# 2_waffling60-DB_matrix.net
KiCad netlist of a schematic drawn in Altium Designer
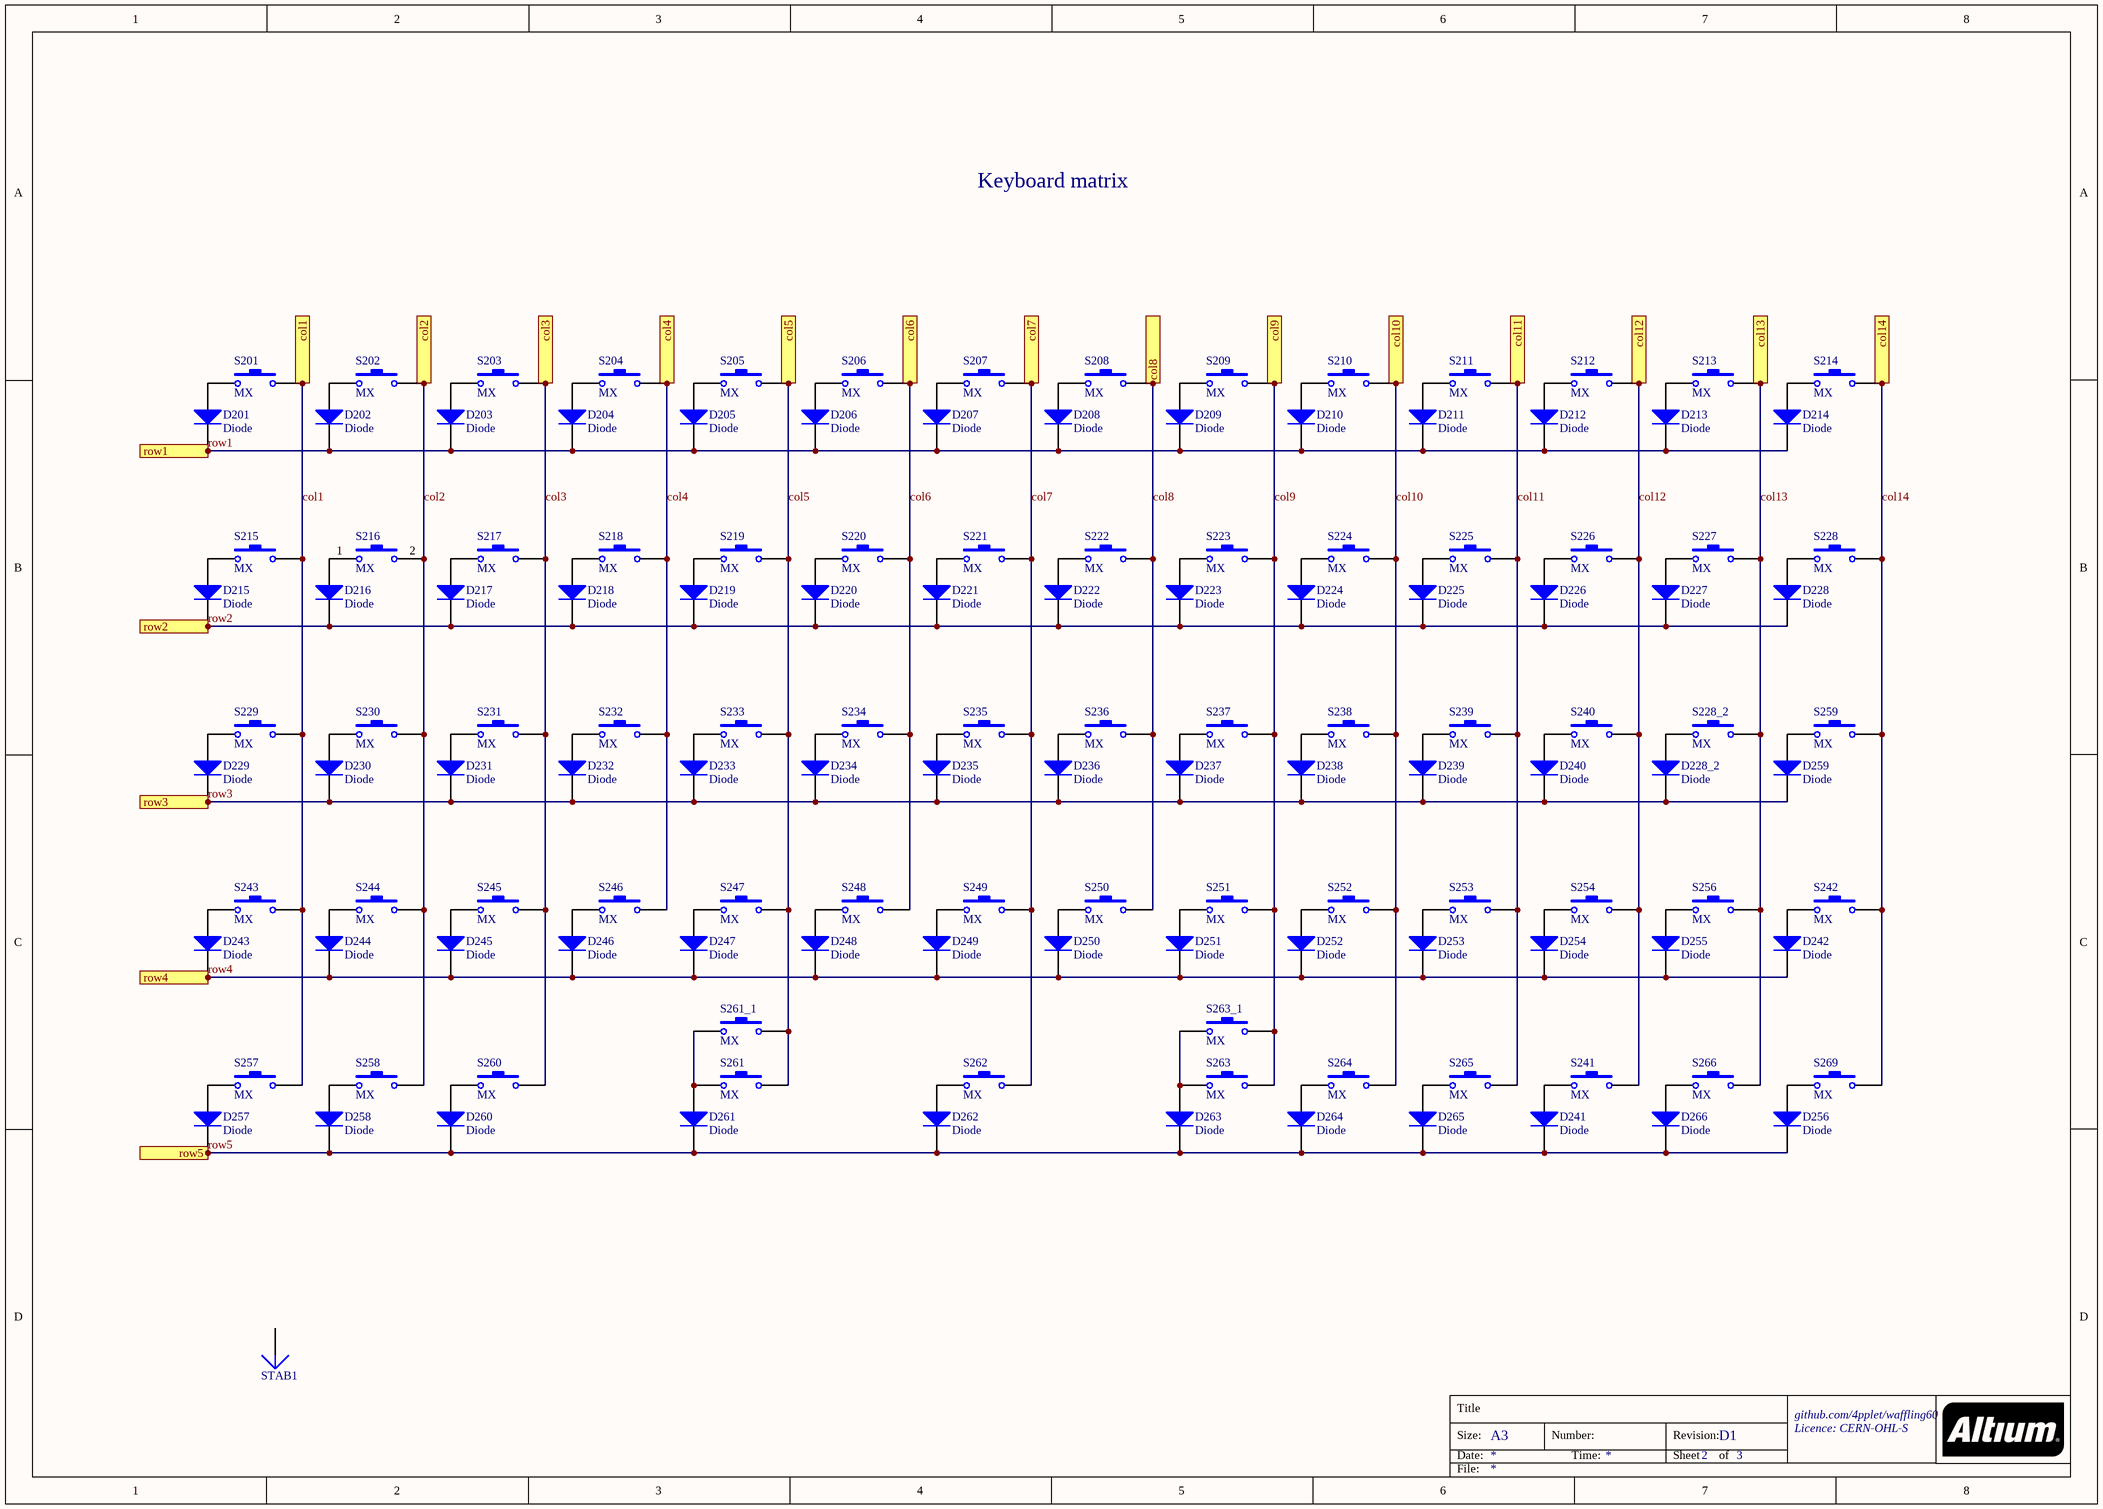
[diagram p0: 2_waffling60-DB_matrix.SchDoc]

(export (version "E")
  (design (tool "Eeschema 10.0.6"))
  (components
    (comp (ref "D201")
      (value "Diode")
      (footprint "SOD-123")
      (description "Default Diode")
      (fields (field (name "LCSC PART #") "C81598") (field (name "MRF.PART") "1N4148W"))
      (libsource (lib "Miscellaneous Devices") (part "Diode"))
    )
    (comp (ref "D202")
      (value "Diode")
      (footprint "SOD-123")
      (description "Default Diode")
      (fields (field (name "LCSC PART #") "C81598") (field (name "MRF.PART") "1N4148W"))
      (libsource (lib "Miscellaneous Devices") (part "Diode"))
    )
    (comp (ref "D203")
      (value "Diode")
      (footprint "SOD-123")
      (description "Default Diode")
      (fields (field (name "LCSC PART #") "C81598") (field (name "MRF.PART") "1N4148W"))
      (libsource (lib "Miscellaneous Devices") (part "Diode"))
    )
    (comp (ref "D204")
      (value "Diode")
      (footprint "SOD-123")
      (description "Default Diode")
      (fields (field (name "LCSC PART #") "C81598") (field (name "MRF.PART") "1N4148W"))
      (libsource (lib "Miscellaneous Devices") (part "Diode"))
    )
    (comp (ref "D205")
      (value "Diode")
      (footprint "SOD-123")
      (description "Default Diode")
      (fields (field (name "LCSC PART #") "C81598") (field (name "MRF.PART") "1N4148W"))
      (libsource (lib "Miscellaneous Devices") (part "Diode"))
    )
    (comp (ref "D206")
      (value "Diode")
      (footprint "SOD-123")
      (description "Default Diode")
      (fields (field (name "LCSC PART #") "C81598") (field (name "MRF.PART") "1N4148W"))
      (libsource (lib "Miscellaneous Devices") (part "Diode"))
    )
    (comp (ref "D207")
      (value "Diode")
      (footprint "SOD-123")
      (description "Default Diode")
      (fields (field (name "LCSC PART #") "C81598") (field (name "MRF.PART") "1N4148W"))
      (libsource (lib "Miscellaneous Devices") (part "Diode"))
    )
    (comp (ref "D208")
      (value "Diode")
      (footprint "SOD-123")
      (description "Default Diode")
      (fields (field (name "LCSC PART #") "C81598") (field (name "MRF.PART") "1N4148W"))
      (libsource (lib "Miscellaneous Devices") (part "Diode"))
    )
    (comp (ref "D209")
      (value "Diode")
      (footprint "SOD-123")
      (description "Default Diode")
      (fields (field (name "LCSC PART #") "C81598") (field (name "MRF.PART") "1N4148W"))
      (libsource (lib "Miscellaneous Devices") (part "Diode"))
    )
    (comp (ref "D210")
      (value "Diode")
      (footprint "SOD-123")
      (description "Default Diode")
      (fields (field (name "LCSC PART #") "C81598") (field (name "MRF.PART") "1N4148W"))
      (libsource (lib "Miscellaneous Devices") (part "Diode"))
    )
    (comp (ref "D211")
      (value "Diode")
      (footprint "SOD-123")
      (description "Default Diode")
      (fields (field (name "LCSC PART #") "C81598") (field (name "MRF.PART") "1N4148W"))
      (libsource (lib "Miscellaneous Devices") (part "Diode"))
    )
    (comp (ref "D212")
      (value "Diode")
      (footprint "SOD-123")
      (description "Default Diode")
      (fields (field (name "LCSC PART #") "C81598") (field (name "MRF.PART") "1N4148W"))
      (libsource (lib "Miscellaneous Devices") (part "Diode"))
    )
    (comp (ref "D213")
      (value "Diode")
      (footprint "SOD-123")
      (description "Default Diode")
      (fields (field (name "LCSC PART #") "C81598") (field (name "MRF.PART") "1N4148W"))
      (libsource (lib "Miscellaneous Devices") (part "Diode"))
    )
    (comp (ref "D214")
      (value "Diode")
      (footprint "SOD-123")
      (description "Default Diode")
      (fields (field (name "LCSC PART #") "C81598") (field (name "MRF.PART") "1N4148W"))
      (libsource (lib "Miscellaneous Devices") (part "Diode"))
    )
    (comp (ref "D215")
      (value "Diode")
      (footprint "SOD-123")
      (description "Default Diode")
      (fields (field (name "LCSC PART #") "C81598") (field (name "MRF.PART") "1N4148W"))
      (libsource (lib "Miscellaneous Devices") (part "Diode"))
    )
    (comp (ref "D216")
      (value "Diode")
      (footprint "SOD-123")
      (description "Default Diode")
      (fields (field (name "LCSC PART #") "C81598") (field (name "MRF.PART") "1N4148W"))
      (libsource (lib "Miscellaneous Devices") (part "Diode"))
    )
    (comp (ref "D217")
      (value "Diode")
      (footprint "SOD-123")
      (description "Default Diode")
      (fields (field (name "LCSC PART #") "C81598") (field (name "MRF.PART") "1N4148W"))
      (libsource (lib "Miscellaneous Devices") (part "Diode"))
    )
    (comp (ref "D218")
      (value "Diode")
      (footprint "SOD-123")
      (description "Default Diode")
      (fields (field (name "LCSC PART #") "C81598") (field (name "MRF.PART") "1N4148W"))
      (libsource (lib "Miscellaneous Devices") (part "Diode"))
    )
    (comp (ref "D219")
      (value "Diode")
      (footprint "SOD-123")
      (description "Default Diode")
      (fields (field (name "LCSC PART #") "C81598") (field (name "MRF.PART") "1N4148W"))
      (libsource (lib "Miscellaneous Devices") (part "Diode"))
    )
    (comp (ref "D220")
      (value "Diode")
      (footprint "SOD-123")
      (description "Default Diode")
      (fields (field (name "LCSC PART #") "C81598") (field (name "MRF.PART") "1N4148W"))
      (libsource (lib "Miscellaneous Devices") (part "Diode"))
    )
    (comp (ref "D221")
      (value "Diode")
      (footprint "SOD-123")
      (description "Default Diode")
      (fields (field (name "LCSC PART #") "C81598") (field (name "MRF.PART") "1N4148W"))
      (libsource (lib "Miscellaneous Devices") (part "Diode"))
    )
    (comp (ref "D222")
      (value "Diode")
      (footprint "SOD-123")
      (description "Default Diode")
      (fields (field (name "LCSC PART #") "C81598") (field (name "MRF.PART") "1N4148W"))
      (libsource (lib "Miscellaneous Devices") (part "Diode"))
    )
    (comp (ref "D223")
      (value "Diode")
      (footprint "SOD-123")
      (description "Default Diode")
      (fields (field (name "LCSC PART #") "C81598") (field (name "MRF.PART") "1N4148W"))
      (libsource (lib "Miscellaneous Devices") (part "Diode"))
    )
    (comp (ref "D224")
      (value "Diode")
      (footprint "SOD-123")
      (description "Default Diode")
      (fields (field (name "LCSC PART #") "C81598") (field (name "MRF.PART") "1N4148W"))
      (libsource (lib "Miscellaneous Devices") (part "Diode"))
    )
    (comp (ref "D225")
      (value "Diode")
      (footprint "SOD-123")
      (description "Default Diode")
      (fields (field (name "LCSC PART #") "C81598") (field (name "MRF.PART") "1N4148W"))
      (libsource (lib "Miscellaneous Devices") (part "Diode"))
    )
    (comp (ref "D226")
      (value "Diode")
      (footprint "SOD-123")
      (description "Default Diode")
      (fields (field (name "LCSC PART #") "C81598") (field (name "MRF.PART") "1N4148W"))
      (libsource (lib "Miscellaneous Devices") (part "Diode"))
    )
    (comp (ref "D227")
      (value "Diode")
      (footprint "SOD-123")
      (description "Default Diode")
      (fields (field (name "LCSC PART #") "C81598") (field (name "MRF.PART") "1N4148W"))
      (libsource (lib "Miscellaneous Devices") (part "Diode"))
    )
    (comp (ref "D228")
      (value "Diode")
      (footprint "SOD-123")
      (description "Default Diode")
      (fields (field (name "LCSC PART #") "C81598") (field (name "MRF.PART") "1N4148W"))
      (libsource (lib "Miscellaneous Devices") (part "Diode"))
    )
    (comp (ref "D228_2")
      (value "Diode")
      (footprint "SOD-123")
      (description "Default Diode")
      (fields (field (name "LCSC PART #") "C81598") (field (name "MRF.PART") "1N4148W"))
      (libsource (lib "Miscellaneous Devices") (part "Diode"))
    )
    (comp (ref "D229")
      (value "Diode")
      (footprint "SOD-123")
      (description "Default Diode")
      (fields (field (name "LCSC PART #") "C81598") (field (name "MRF.PART") "1N4148W"))
      (libsource (lib "Miscellaneous Devices") (part "Diode"))
    )
    (comp (ref "D230")
      (value "Diode")
      (footprint "SOD-123")
      (description "Default Diode")
      (fields (field (name "LCSC PART #") "C81598") (field (name "MRF.PART") "1N4148W"))
      (libsource (lib "Miscellaneous Devices") (part "Diode"))
    )
    (comp (ref "D231")
      (value "Diode")
      (footprint "SOD-123")
      (description "Default Diode")
      (fields (field (name "LCSC PART #") "C81598") (field (name "MRF.PART") "1N4148W"))
      (libsource (lib "Miscellaneous Devices") (part "Diode"))
    )
    (comp (ref "D232")
      (value "Diode")
      (footprint "SOD-123")
      (description "Default Diode")
      (fields (field (name "LCSC PART #") "C81598") (field (name "MRF.PART") "1N4148W"))
      (libsource (lib "Miscellaneous Devices") (part "Diode"))
    )
    (comp (ref "D233")
      (value "Diode")
      (footprint "SOD-123")
      (description "Default Diode")
      (fields (field (name "LCSC PART #") "C81598") (field (name "MRF.PART") "1N4148W"))
      (libsource (lib "Miscellaneous Devices") (part "Diode"))
    )
    (comp (ref "D234")
      (value "Diode")
      (footprint "SOD-123")
      (description "Default Diode")
      (fields (field (name "LCSC PART #") "C81598") (field (name "MRF.PART") "1N4148W"))
      (libsource (lib "Miscellaneous Devices") (part "Diode"))
    )
    (comp (ref "D235")
      (value "Diode")
      (footprint "SOD-123")
      (description "Default Diode")
      (fields (field (name "LCSC PART #") "C81598") (field (name "MRF.PART") "1N4148W"))
      (libsource (lib "Miscellaneous Devices") (part "Diode"))
    )
    (comp (ref "D236")
      (value "Diode")
      (footprint "SOD-123")
      (description "Default Diode")
      (fields (field (name "LCSC PART #") "C81598") (field (name "MRF.PART") "1N4148W"))
      (libsource (lib "Miscellaneous Devices") (part "Diode"))
    )
    (comp (ref "D237")
      (value "Diode")
      (footprint "SOD-123")
      (description "Default Diode")
      (fields (field (name "LCSC PART #") "C81598") (field (name "MRF.PART") "1N4148W"))
      (libsource (lib "Miscellaneous Devices") (part "Diode"))
    )
    (comp (ref "D238")
      (value "Diode")
      (footprint "SOD-123")
      (description "Default Diode")
      (fields (field (name "LCSC PART #") "C81598") (field (name "MRF.PART") "1N4148W"))
      (libsource (lib "Miscellaneous Devices") (part "Diode"))
    )
    (comp (ref "D239")
      (value "Diode")
      (footprint "SOD-123")
      (description "Default Diode")
      (fields (field (name "LCSC PART #") "C81598") (field (name "MRF.PART") "1N4148W"))
      (libsource (lib "Miscellaneous Devices") (part "Diode"))
    )
    (comp (ref "D240")
      (value "Diode")
      (footprint "SOD-123")
      (description "Default Diode")
      (fields (field (name "LCSC PART #") "C81598") (field (name "MRF.PART") "1N4148W"))
      (libsource (lib "Miscellaneous Devices") (part "Diode"))
    )
    (comp (ref "D241")
      (value "Diode")
      (footprint "SOD-123")
      (description "Default Diode")
      (fields (field (name "LCSC PART #") "C81598") (field (name "MRF.PART") "1N4148W"))
      (libsource (lib "Miscellaneous Devices") (part "Diode"))
    )
    (comp (ref "D242")
      (value "Diode")
      (footprint "SOD-123")
      (description "Default Diode")
      (fields (field (name "LCSC PART #") "C81598") (field (name "MRF.PART") "1N4148W"))
      (libsource (lib "Miscellaneous Devices") (part "Diode"))
    )
    (comp (ref "D243")
      (value "Diode")
      (footprint "SOD-123")
      (description "Default Diode")
      (fields (field (name "LCSC PART #") "C81598") (field (name "MRF.PART") "1N4148W"))
      (libsource (lib "Miscellaneous Devices") (part "Diode"))
    )
    (comp (ref "D244")
      (value "Diode")
      (footprint "SOD-123")
      (description "Default Diode")
      (fields (field (name "LCSC PART #") "C81598") (field (name "MRF.PART") "1N4148W"))
      (libsource (lib "Miscellaneous Devices") (part "Diode"))
    )
    (comp (ref "D245")
      (value "Diode")
      (footprint "SOD-123")
      (description "Default Diode")
      (fields (field (name "LCSC PART #") "C81598") (field (name "MRF.PART") "1N4148W"))
      (libsource (lib "Miscellaneous Devices") (part "Diode"))
    )
    (comp (ref "D246")
      (value "Diode")
      (footprint "SOD-123")
      (description "Default Diode")
      (fields (field (name "LCSC PART #") "C81598") (field (name "MRF.PART") "1N4148W"))
      (libsource (lib "Miscellaneous Devices") (part "Diode"))
    )
    (comp (ref "D247")
      (value "Diode")
      (footprint "SOD-123")
      (description "Default Diode")
      (fields (field (name "LCSC PART #") "C81598") (field (name "MRF.PART") "1N4148W"))
      (libsource (lib "Miscellaneous Devices") (part "Diode"))
    )
    (comp (ref "D248")
      (value "Diode")
      (footprint "SOD-123")
      (description "Default Diode")
      (fields (field (name "LCSC PART #") "C81598") (field (name "MRF.PART") "1N4148W"))
      (libsource (lib "Miscellaneous Devices") (part "Diode"))
    )
    (comp (ref "D249")
      (value "Diode")
      (footprint "SOD-123")
      (description "Default Diode")
      (fields (field (name "LCSC PART #") "C81598") (field (name "MRF.PART") "1N4148W"))
      (libsource (lib "Miscellaneous Devices") (part "Diode"))
    )
    (comp (ref "D250")
      (value "Diode")
      (footprint "SOD-123")
      (description "Default Diode")
      (fields (field (name "LCSC PART #") "C81598") (field (name "MRF.PART") "1N4148W"))
      (libsource (lib "Miscellaneous Devices") (part "Diode"))
    )
    (comp (ref "D251")
      (value "Diode")
      (footprint "SOD-123")
      (description "Default Diode")
      (fields (field (name "LCSC PART #") "C81598") (field (name "MRF.PART") "1N4148W"))
      (libsource (lib "Miscellaneous Devices") (part "Diode"))
    )
    (comp (ref "D252")
      (value "Diode")
      (footprint "SOD-123")
      (description "Default Diode")
      (fields (field (name "LCSC PART #") "C81598") (field (name "MRF.PART") "1N4148W"))
      (libsource (lib "Miscellaneous Devices") (part "Diode"))
    )
    (comp (ref "D253")
      (value "Diode")
      (footprint "SOD-123")
      (description "Default Diode")
      (fields (field (name "LCSC PART #") "C81598") (field (name "MRF.PART") "1N4148W"))
      (libsource (lib "Miscellaneous Devices") (part "Diode"))
    )
    (comp (ref "D254")
      (value "Diode")
      (footprint "SOD-123")
      (description "Default Diode")
      (fields (field (name "LCSC PART #") "C81598") (field (name "MRF.PART") "1N4148W"))
      (libsource (lib "Miscellaneous Devices") (part "Diode"))
    )
    (comp (ref "D255")
      (value "Diode")
      (footprint "SOD-123")
      (description "Default Diode")
      (fields (field (name "LCSC PART #") "C81598") (field (name "MRF.PART") "1N4148W"))
      (libsource (lib "Miscellaneous Devices") (part "Diode"))
    )
    (comp (ref "D256")
      (value "Diode")
      (footprint "SOD-123")
      (description "Default Diode")
      (fields (field (name "LCSC PART #") "C81598") (field (name "MRF.PART") "1N4148W"))
      (libsource (lib "Miscellaneous Devices") (part "Diode"))
    )
    (comp (ref "D257")
      (value "Diode")
      (footprint "SOD-123")
      (description "Default Diode")
      (fields (field (name "LCSC PART #") "C81598") (field (name "MRF.PART") "1N4148W"))
      (libsource (lib "Miscellaneous Devices") (part "Diode"))
    )
    (comp (ref "D258")
      (value "Diode")
      (footprint "SOD-123")
      (description "Default Diode")
      (fields (field (name "LCSC PART #") "C81598") (field (name "MRF.PART") "1N4148W"))
      (libsource (lib "Miscellaneous Devices") (part "Diode"))
    )
    (comp (ref "D259")
      (value "Diode")
      (footprint "SOD-123")
      (description "Default Diode")
      (fields (field (name "LCSC PART #") "C81598") (field (name "MRF.PART") "1N4148W"))
      (libsource (lib "Miscellaneous Devices") (part "Diode"))
    )
    (comp (ref "D260")
      (value "Diode")
      (footprint "SOD-123")
      (description "Default Diode")
      (fields (field (name "LCSC PART #") "C81598") (field (name "MRF.PART") "1N4148W"))
      (libsource (lib "Miscellaneous Devices") (part "Diode"))
    )
    (comp (ref "D261")
      (value "Diode")
      (footprint "SOD-123")
      (description "Default Diode")
      (fields (field (name "LCSC PART #") "C81598") (field (name "MRF.PART") "1N4148W"))
      (libsource (lib "Miscellaneous Devices") (part "Diode"))
    )
    (comp (ref "D262")
      (value "Diode")
      (footprint "SOD-123")
      (description "Default Diode")
      (fields (field (name "LCSC PART #") "C81598") (field (name "MRF.PART") "1N4148W"))
      (libsource (lib "Miscellaneous Devices") (part "Diode"))
    )
    (comp (ref "D263")
      (value "Diode")
      (footprint "SOD-123")
      (description "Default Diode")
      (fields (field (name "LCSC PART #") "C81598") (field (name "MRF.PART") "1N4148W"))
      (libsource (lib "Miscellaneous Devices") (part "Diode"))
    )
    (comp (ref "D264")
      (value "Diode")
      (footprint "SOD-123")
      (description "Default Diode")
      (fields (field (name "LCSC PART #") "C81598") (field (name "MRF.PART") "1N4148W"))
      (libsource (lib "Miscellaneous Devices") (part "Diode"))
    )
    (comp (ref "D265")
      (value "Diode")
      (footprint "SOD-123")
      (description "Default Diode")
      (fields (field (name "LCSC PART #") "C81598") (field (name "MRF.PART") "1N4148W"))
      (libsource (lib "Miscellaneous Devices") (part "Diode"))
    )
    (comp (ref "D266")
      (value "Diode")
      (footprint "SOD-123")
      (description "Default Diode")
      (fields (field (name "LCSC PART #") "C81598") (field (name "MRF.PART") "1N4148W"))
      (libsource (lib "Miscellaneous Devices") (part "Diode"))
    )
    (comp (ref "S201")
      (value "MX")
      (footprint "MX-switch - switched pol")
      (description "Switch")
      (libsource (lib "Miscellaneous Devices") (part "SW-PB"))
    )
    (comp (ref "S202")
      (value "MX")
      (footprint "MX-switch")
      (description "Switch")
      (libsource (lib "Miscellaneous Devices") (part "SW-PB"))
    )
    (comp (ref "S203")
      (value "MX")
      (footprint "MX-switch - switched pol")
      (description "Switch")
      (libsource (lib "Miscellaneous Devices") (part "SW-PB"))
    )
    (comp (ref "S204")
      (value "MX")
      (footprint "MX-switch - switched pol")
      (description "Switch")
      (libsource (lib "Miscellaneous Devices") (part "SW-PB"))
    )
    (comp (ref "S205")
      (value "MX")
      (footprint "MX-switch - switched pol")
      (description "Switch")
      (libsource (lib "Miscellaneous Devices") (part "SW-PB"))
    )
    (comp (ref "S206")
      (value "MX")
      (footprint "MX-switch - switched pol")
      (description "Switch")
      (libsource (lib "Miscellaneous Devices") (part "SW-PB"))
    )
    (comp (ref "S207")
      (value "MX")
      (footprint "MX-switch - switched pol")
      (description "Switch")
      (libsource (lib "Miscellaneous Devices") (part "SW-PB"))
    )
    (comp (ref "S208")
      (value "MX")
      (footprint "MX-switch - switched pol")
      (description "Switch")
      (libsource (lib "Miscellaneous Devices") (part "SW-PB"))
    )
    (comp (ref "S209")
      (value "MX")
      (footprint "MX-switch - switched pol")
      (description "Switch")
      (libsource (lib "Miscellaneous Devices") (part "SW-PB"))
    )
    (comp (ref "S210")
      (value "MX")
      (footprint "MX-switch - switched pol")
      (description "Switch")
      (libsource (lib "Miscellaneous Devices") (part "SW-PB"))
    )
    (comp (ref "S211")
      (value "MX")
      (footprint "MX-switch - switched pol")
      (description "Switch")
      (libsource (lib "Miscellaneous Devices") (part "SW-PB"))
    )
    (comp (ref "S212")
      (value "MX")
      (footprint "MX-switch - switched pol")
      (description "Switch")
      (libsource (lib "Miscellaneous Devices") (part "SW-PB"))
    )
    (comp (ref "S213")
      (value "MX")
      (footprint "MX-switch - switched pol")
      (description "Switch")
      (libsource (lib "Miscellaneous Devices") (part "SW-PB"))
    )
    (comp (ref "S214")
      (value "MX")
      (footprint "MX-switch")
      (description "Switch")
      (libsource (lib "Miscellaneous Devices") (part "SW-PB"))
    )
    (comp (ref "S215")
      (value "MX")
      (footprint "MX-switch - switched pol")
      (description "TAB")
      (libsource (lib "Miscellaneous Devices") (part "SW-PB"))
    )
    (comp (ref "S216")
      (value "MX")
      (footprint "MX-switch")
      (description "Switch")
      (libsource (lib "") (part "SW-PB_1"))
    )
    (comp (ref "S217")
      (value "MX")
      (footprint "MX-switch - switched pol")
      (description "Switch")
      (libsource (lib "Miscellaneous Devices") (part "SW-PB"))
    )
    (comp (ref "S218")
      (value "MX")
      (footprint "MX-switch - switched pol")
      (description "Switch")
      (libsource (lib "Miscellaneous Devices") (part "SW-PB"))
    )
    (comp (ref "S219")
      (value "MX")
      (footprint "MX-switch - switched pol")
      (description "Switch")
      (libsource (lib "Miscellaneous Devices") (part "SW-PB"))
    )
    (comp (ref "S220")
      (value "MX")
      (footprint "MX-switch")
      (description "Switch")
      (libsource (lib "Miscellaneous Devices") (part "SW-PB"))
    )
    (comp (ref "S221")
      (value "MX")
      (footprint "MX-switch - switched pol")
      (description "Switch")
      (libsource (lib "Miscellaneous Devices") (part "SW-PB"))
    )
    (comp (ref "S222")
      (value "MX")
      (footprint "MX-switch")
      (description "Switch")
      (libsource (lib "Miscellaneous Devices") (part "SW-PB"))
    )
    (comp (ref "S223")
      (value "MX")
      (footprint "MX-switch - switched pol")
      (description "Switch")
      (libsource (lib "Miscellaneous Devices") (part "SW-PB"))
    )
    (comp (ref "S224")
      (value "MX")
      (footprint "MX-switch - switched pol")
      (description "Switch")
      (libsource (lib "Miscellaneous Devices") (part "SW-PB"))
    )
    (comp (ref "S225")
      (value "MX")
      (footprint "MX-switch - switched pol")
      (description "Switch")
      (libsource (lib "Miscellaneous Devices") (part "SW-PB"))
    )
    (comp (ref "S226")
      (value "MX")
      (footprint "MX-switch")
      (description "Switch")
      (libsource (lib "Miscellaneous Devices") (part "SW-PB"))
    )
    (comp (ref "S227")
      (value "MX")
      (footprint "MX-switch")
      (description "Switch")
      (libsource (lib "Miscellaneous Devices") (part "SW-PB"))
    )
    (comp (ref "S228")
      (value "MX")
      (footprint "MX-switch - 1.5U")
      (description "Switch")
      (libsource (lib "Miscellaneous Devices") (part "SW-PB"))
    )
    (comp (ref "S228_2")
      (value "MX")
      (footprint "MX-switch")
      (description "Switch")
      (libsource (lib "Miscellaneous Devices") (part "SW-PB"))
    )
    (comp (ref "S229")
      (value "MX")
      (footprint "MX-switch - CAPS")
      (description "Switch")
      (libsource (lib "Miscellaneous Devices") (part "SW-PB"))
    )
    (comp (ref "S230")
      (value "MX")
      (footprint "MX-switch")
      (description "Switch")
      (libsource (lib "Miscellaneous Devices") (part "SW-PB"))
    )
    (comp (ref "S231")
      (value "MX")
      (footprint "MX-switch - switched pol")
      (description "Switch")
      (libsource (lib "Miscellaneous Devices") (part "SW-PB"))
    )
    (comp (ref "S232")
      (value "MX")
      (footprint "MX-switch - switched pol")
      (description "Switch")
      (libsource (lib "Miscellaneous Devices") (part "SW-PB"))
    )
    (comp (ref "S233")
      (value "MX")
      (footprint "MX-switch - switched pol")
      (description "Switch")
      (libsource (lib "Miscellaneous Devices") (part "SW-PB"))
    )
    (comp (ref "S234")
      (value "MX")
      (footprint "MX-switch - switched pol")
      (description "Switch")
      (libsource (lib "Miscellaneous Devices") (part "SW-PB"))
    )
    (comp (ref "S235")
      (value "MX")
      (footprint "MX-switch - switched pol")
      (description "Switch")
      (libsource (lib "Miscellaneous Devices") (part "SW-PB"))
    )
    (comp (ref "S236")
      (value "MX")
      (footprint "MX-switch - switched pol")
      (description "Switch")
      (libsource (lib "Miscellaneous Devices") (part "SW-PB"))
    )
    (comp (ref "S237")
      (value "MX")
      (footprint "MX-switch - switched pol")
      (description "Switch")
      (libsource (lib "Miscellaneous Devices") (part "SW-PB"))
    )
    (comp (ref "S238")
      (value "MX")
      (footprint "MX-switch - switched pol")
      (description "Switch")
      (libsource (lib "Miscellaneous Devices") (part "SW-PB"))
    )
    (comp (ref "S239")
      (value "MX")
      (footprint "MX-switch - switched pol")
      (description "Switch")
      (libsource (lib "Miscellaneous Devices") (part "SW-PB"))
    )
    (comp (ref "S240")
      (value "MX")
      (footprint "MX-switch - switched pol")
      (description "Switch")
      (libsource (lib "Miscellaneous Devices") (part "SW-PB"))
    )
    (comp (ref "S241")
      (value "MX")
      (footprint "MX-switch - 1u MOD-R")
      (description "Switch")
      (libsource (lib "Miscellaneous Devices") (part "SW-PB"))
    )
    (comp (ref "S242")
      (value "MX")
      (footprint "MX-switch - Enter - Rotated Stab")
      (description "Switch")
      (libsource (lib "Miscellaneous Devices") (part "SW-PB"))
    )
    (comp (ref "S243")
      (value "MX")
      (footprint "MX-switch - Left shift")
      (description "Switch")
      (libsource (lib "Miscellaneous Devices") (part "SW-PB"))
    )
    (comp (ref "S244")
      (value "MX")
      (footprint "MX-switch")
      (description "Switch")
      (libsource (lib "Miscellaneous Devices") (part "SW-PB"))
    )
    (comp (ref "S245")
      (value "MX")
      (footprint "MX-switch - switched pol")
      (description "Switch")
      (libsource (lib "Miscellaneous Devices") (part "SW-PB"))
    )
    (comp (ref "S246")
      (value "MX")
      (footprint "MX-switch - switched pol")
      (description "Switch")
      (libsource (lib "Miscellaneous Devices") (part "SW-PB"))
    )
    (comp (ref "S247")
      (value "MX")
      (footprint "MX-switch - switched pol")
      (description "Switch")
      (libsource (lib "Miscellaneous Devices") (part "SW-PB"))
    )
    (comp (ref "S248")
      (value "MX")
      (footprint "MX-switch - switched pol")
      (description "Switch")
      (libsource (lib "Miscellaneous Devices") (part "SW-PB"))
    )
    (comp (ref "S249")
      (value "MX")
      (footprint "MX-switch - switched pol")
      (description "Switch")
      (libsource (lib "Miscellaneous Devices") (part "SW-PB"))
    )
    (comp (ref "S250")
      (value "MX")
      (footprint "MX-switch - switched pol")
      (description "Switch")
      (libsource (lib "Miscellaneous Devices") (part "SW-PB"))
    )
    (comp (ref "S251")
      (value "MX")
      (footprint "MX-switch - switched pol")
      (description "Switch")
      (libsource (lib "Miscellaneous Devices") (part "SW-PB"))
    )
    (comp (ref "S252")
      (value "MX")
      (footprint "MX-switch - switched pol")
      (description "Switch")
      (libsource (lib "Miscellaneous Devices") (part "SW-PB"))
    )
    (comp (ref "S253")
      (value "MX")
      (footprint "MX-switch - switched pol")
      (description "Switch")
      (libsource (lib "Miscellaneous Devices") (part "SW-PB"))
    )
    (comp (ref "S254")
      (value "MX")
      (footprint "MX-switch - switched pol")
      (description "Switch")
      (libsource (lib "Miscellaneous Devices") (part "SW-PB"))
    )
    (comp (ref "S256")
      (value "MX")
      (footprint "MX-switch - right shift")
      (description "Switch")
      (libsource (lib "Miscellaneous Devices") (part "SW-PB"))
    )
    (comp (ref "S257")
      (value "MX")
      (footprint "MX-switch - 1.5u MOD-L")
      (description "Switch")
      (libsource (lib "Miscellaneous Devices") (part "SW-PB"))
    )
    (comp (ref "S258")
      (value "MX")
      (footprint "MX-switch - 1u MOD-L")
      (description "Switch")
      (libsource (lib "Miscellaneous Devices") (part "SW-PB"))
    )
    (comp (ref "S259")
      (value "MX")
      (footprint "MX-switch - backspace")
      (description "Switch")
      (libsource (lib "Miscellaneous Devices") (part "SW-PB"))
    )
    (comp (ref "S260")
      (value "MX")
      (footprint "MX-switch - 1.5u MOD-L")
      (description "Switch")
      (libsource (lib "Miscellaneous Devices") (part "SW-PB"))
    )
    (comp (ref "S261")
      (value "MX")
      (footprint "MX-SWITCH - L SPLIT SPACE_V2")
      (description "Switch")
      (libsource (lib "Miscellaneous Devices") (part "SW-PB"))
    )
    (comp (ref "S261_1")
      (value "MX")
      (footprint "MX-switch - 3U - rotated stab")
      (description "Switch")
      (libsource (lib "Miscellaneous Devices") (part "SW-PB"))
    )
    (comp (ref "S262")
      (value "MX")
      (footprint "MX-switch - Space_V3")
      (description "Switch")
      (libsource (lib "Miscellaneous Devices") (part "SW-PB"))
    )
    (comp (ref "S263")
      (value "MX")
      (footprint "MX-SWITCH - R SPLIT SPACE_V2")
      (description "Switch")
      (libsource (lib "Miscellaneous Devices") (part "SW-PB"))
    )
    (comp (ref "S263_1")
      (value "MX")
      (footprint "MX-switch - 3U - rotated stab")
      (description "Switch")
      (libsource (lib "Miscellaneous Devices") (part "SW-PB"))
    )
    (comp (ref "S264")
      (value "MX")
      (footprint "MX-switch - switched pol")
      (description "Switch")
      (libsource (lib "Miscellaneous Devices") (part "SW-PB"))
    )
    (comp (ref "S265")
      (value "MX")
      (footprint "MX-switch - 1.5u MOD-R")
      (description "Switch")
      (libsource (lib "Miscellaneous Devices") (part "SW-PB"))
    )
    (comp (ref "S266")
      (value "MX")
      (footprint "MX-switch - 1.5u MOD-R")
      (description "Switch")
      (libsource (lib "Miscellaneous Devices") (part "SW-PB"))
    )
    (comp (ref "S269")
      (value "MX")
      (footprint "MX-switch")
      (description "Switch")
      (libsource (lib "Miscellaneous Devices") (part "SW-PB"))
    )
    (comp (ref "STAB1")
      (value "Plug")
      (footprint "Stab 10U")
      (libsource (lib "Miscellaneous Connectors") (part "Plug"))
    )
  )
  (nets
    (net (code "1") (name "/col1") (class "Default")
      (node (ref "S201") (pin "2") (pinfunction "2_2") (pintype "passive"))
      (node (ref "S215") (pin "2") (pinfunction "2_2") (pintype "passive"))
      (node (ref "S229") (pin "1") (pinfunction "1_1") (pintype "passive"))
      (node (ref "S243") (pin "2") (pinfunction "2_2") (pintype "passive"))
      (node (ref "S257") (pin "1") (pinfunction "1_1") (pintype "passive"))
    )
    (net (code "2") (name "/col2") (class "Default")
      (node (ref "S202") (pin "2") (pinfunction "2_2") (pintype "passive"))
      (node (ref "S216") (pin "2") (pinfunction "2_2") (pintype "passive"))
      (node (ref "S230") (pin "2") (pinfunction "2_2") (pintype "passive"))
      (node (ref "S244") (pin "1") (pinfunction "1_1") (pintype "passive"))
      (node (ref "S258") (pin "2") (pinfunction "2_2") (pintype "passive"))
    )
    (net (code "3") (name "/col3") (class "Default")
      (node (ref "S203") (pin "2") (pinfunction "2_2") (pintype "passive"))
      (node (ref "S217") (pin "2") (pinfunction "2_2") (pintype "passive"))
      (node (ref "S231") (pin "2") (pinfunction "2_2") (pintype "passive"))
      (node (ref "S245") (pin "2") (pinfunction "2_2") (pintype "passive"))
      (node (ref "S260") (pin "2") (pinfunction "2_2") (pintype "passive"))
    )
    (net (code "4") (name "/col4") (class "Default")
      (node (ref "S204") (pin "2") (pinfunction "2_2") (pintype "passive"))
      (node (ref "S218") (pin "2") (pinfunction "2_2") (pintype "passive"))
      (node (ref "S232") (pin "2") (pinfunction "2_2") (pintype "passive"))
      (node (ref "S246") (pin "2") (pinfunction "2_2") (pintype "passive"))
    )
    (net (code "5") (name "/col5") (class "Default")
      (node (ref "S205") (pin "2") (pinfunction "2_2") (pintype "passive"))
      (node (ref "S219") (pin "2") (pinfunction "2_2") (pintype "passive"))
      (node (ref "S233") (pin "2") (pinfunction "2_2") (pintype "passive"))
      (node (ref "S247") (pin "2") (pinfunction "2_2") (pintype "passive"))
      (node (ref "S261") (pin "2") (pinfunction "2_2") (pintype "passive"))
      (node (ref "S261_1") (pin "2") (pinfunction "2_2") (pintype "passive"))
    )
    (net (code "6") (name "/col6") (class "Default")
      (node (ref "S206") (pin "2") (pinfunction "2_2") (pintype "passive"))
      (node (ref "S220") (pin "2") (pinfunction "2_2") (pintype "passive"))
      (node (ref "S234") (pin "2") (pinfunction "2_2") (pintype "passive"))
      (node (ref "S248") (pin "2") (pinfunction "2_2") (pintype "passive"))
    )
    (net (code "7") (name "/col7") (class "Default")
      (node (ref "S207") (pin "2") (pinfunction "2_2") (pintype "passive"))
      (node (ref "S221") (pin "2") (pinfunction "2_2") (pintype "passive"))
      (node (ref "S235") (pin "2") (pinfunction "2_2") (pintype "passive"))
      (node (ref "S249") (pin "2") (pinfunction "2_2") (pintype "passive"))
      (node (ref "S262") (pin "1") (pinfunction "1_1") (pintype "passive"))
    )
    (net (code "8") (name "/col8") (class "Default")
      (node (ref "S208") (pin "2") (pinfunction "2_2") (pintype "passive"))
      (node (ref "S222") (pin "2") (pinfunction "2_2") (pintype "passive"))
      (node (ref "S236") (pin "2") (pinfunction "2_2") (pintype "passive"))
      (node (ref "S250") (pin "2") (pinfunction "2_2") (pintype "passive"))
    )
    (net (code "9") (name "/col9") (class "Default")
      (node (ref "S209") (pin "2") (pinfunction "2_2") (pintype "passive"))
      (node (ref "S223") (pin "2") (pinfunction "2_2") (pintype "passive"))
      (node (ref "S237") (pin "2") (pinfunction "2_2") (pintype "passive"))
      (node (ref "S251") (pin "2") (pinfunction "2_2") (pintype "passive"))
      (node (ref "S263") (pin "1") (pinfunction "1_1") (pintype "passive"))
      (node (ref "S263_1") (pin "1") (pinfunction "1_1") (pintype "passive"))
    )
    (net (code "10") (name "/col10") (class "Default")
      (node (ref "S210") (pin "2") (pinfunction "2_2") (pintype "passive"))
      (node (ref "S224") (pin "2") (pinfunction "2_2") (pintype "passive"))
      (node (ref "S238") (pin "2") (pinfunction "2_2") (pintype "passive"))
      (node (ref "S252") (pin "2") (pinfunction "2_2") (pintype "passive"))
      (node (ref "S264") (pin "2") (pinfunction "2_2") (pintype "passive"))
    )
    (net (code "11") (name "/col11") (class "Default")
      (node (ref "S211") (pin "2") (pinfunction "2_2") (pintype "passive"))
      (node (ref "S225") (pin "2") (pinfunction "2_2") (pintype "passive"))
      (node (ref "S239") (pin "2") (pinfunction "2_2") (pintype "passive"))
      (node (ref "S253") (pin "2") (pinfunction "2_2") (pintype "passive"))
      (node (ref "S265") (pin "1") (pinfunction "1_1") (pintype "passive"))
    )
    (net (code "12") (name "/col12") (class "Default")
      (node (ref "S212") (pin "2") (pinfunction "2_2") (pintype "passive"))
      (node (ref "S226") (pin "2") (pinfunction "2_2") (pintype "passive"))
      (node (ref "S240") (pin "2") (pinfunction "2_2") (pintype "passive"))
      (node (ref "S241") (pin "1") (pinfunction "1_1") (pintype "passive"))
      (node (ref "S254") (pin "2") (pinfunction "2_2") (pintype "passive"))
    )
    (net (code "13") (name "/col13") (class "Default")
      (node (ref "S213") (pin "2") (pinfunction "2_2") (pintype "passive"))
      (node (ref "S227") (pin "2") (pinfunction "2_2") (pintype "passive"))
      (node (ref "S228_2") (pin "2") (pinfunction "2_2") (pintype "passive"))
      (node (ref "S256") (pin "2") (pinfunction "2_2") (pintype "passive"))
      (node (ref "S266") (pin "2") (pinfunction "2_2") (pintype "passive"))
    )
    (net (code "14") (name "/col14") (class "Default")
      (node (ref "S214") (pin "2") (pinfunction "2_2") (pintype "passive"))
      (node (ref "S228") (pin "2") (pinfunction "2_2") (pintype "passive"))
      (node (ref "S242") (pin "2") (pinfunction "2_2") (pintype "passive"))
      (node (ref "S259") (pin "2") (pinfunction "2_2") (pintype "passive"))
      (node (ref "S269") (pin "2") (pinfunction "2_2") (pintype "passive"))
    )
    (net (code "15") (name "/row1") (class "Default")
      (node (ref "D201") (pin "2") (pinfunction "K_2") (pintype "passive"))
      (node (ref "D202") (pin "2") (pinfunction "K_2") (pintype "passive"))
      (node (ref "D203") (pin "2") (pinfunction "K_2") (pintype "passive"))
      (node (ref "D204") (pin "2") (pinfunction "K_2") (pintype "passive"))
      (node (ref "D205") (pin "2") (pinfunction "K_2") (pintype "passive"))
      (node (ref "D206") (pin "2") (pinfunction "K_2") (pintype "passive"))
      (node (ref "D207") (pin "2") (pinfunction "K_2") (pintype "passive"))
      (node (ref "D208") (pin "2") (pinfunction "K_2") (pintype "passive"))
      (node (ref "D209") (pin "2") (pinfunction "K_2") (pintype "passive"))
      (node (ref "D210") (pin "2") (pinfunction "K_2") (pintype "passive"))
      (node (ref "D211") (pin "2") (pinfunction "K_2") (pintype "passive"))
      (node (ref "D212") (pin "2") (pinfunction "K_2") (pintype "passive"))
      (node (ref "D213") (pin "2") (pinfunction "K_2") (pintype "passive"))
      (node (ref "D214") (pin "2") (pinfunction "K_2") (pintype "passive"))
    )
    (net (code "16") (name "/row2") (class "Default")
      (node (ref "D215") (pin "2") (pinfunction "K_2") (pintype "passive"))
      (node (ref "D216") (pin "2") (pinfunction "K_2") (pintype "passive"))
      (node (ref "D217") (pin "2") (pinfunction "K_2") (pintype "passive"))
      (node (ref "D218") (pin "2") (pinfunction "K_2") (pintype "passive"))
      (node (ref "D219") (pin "2") (pinfunction "K_2") (pintype "passive"))
      (node (ref "D220") (pin "2") (pinfunction "K_2") (pintype "passive"))
      (node (ref "D221") (pin "2") (pinfunction "K_2") (pintype "passive"))
      (node (ref "D222") (pin "2") (pinfunction "K_2") (pintype "passive"))
      (node (ref "D223") (pin "2") (pinfunction "K_2") (pintype "passive"))
      (node (ref "D224") (pin "2") (pinfunction "K_2") (pintype "passive"))
      (node (ref "D225") (pin "2") (pinfunction "K_2") (pintype "passive"))
      (node (ref "D226") (pin "2") (pinfunction "K_2") (pintype "passive"))
      (node (ref "D227") (pin "2") (pinfunction "K_2") (pintype "passive"))
      (node (ref "D228") (pin "2") (pinfunction "K_2") (pintype "passive"))
    )
    (net (code "17") (name "/row3") (class "Default")
      (node (ref "D228_2") (pin "2") (pinfunction "K_2") (pintype "passive"))
      (node (ref "D229") (pin "2") (pinfunction "K_2") (pintype "passive"))
      (node (ref "D230") (pin "2") (pinfunction "K_2") (pintype "passive"))
      (node (ref "D231") (pin "2") (pinfunction "K_2") (pintype "passive"))
      (node (ref "D232") (pin "2") (pinfunction "K_2") (pintype "passive"))
      (node (ref "D233") (pin "2") (pinfunction "K_2") (pintype "passive"))
      (node (ref "D234") (pin "2") (pinfunction "K_2") (pintype "passive"))
      (node (ref "D235") (pin "2") (pinfunction "K_2") (pintype "passive"))
      (node (ref "D236") (pin "2") (pinfunction "K_2") (pintype "passive"))
      (node (ref "D237") (pin "2") (pinfunction "K_2") (pintype "passive"))
      (node (ref "D238") (pin "2") (pinfunction "K_2") (pintype "passive"))
      (node (ref "D239") (pin "2") (pinfunction "K_2") (pintype "passive"))
      (node (ref "D240") (pin "2") (pinfunction "K_2") (pintype "passive"))
      (node (ref "D259") (pin "2") (pinfunction "K_2") (pintype "passive"))
    )
    (net (code "18") (name "/row4") (class "Default")
      (node (ref "D242") (pin "2") (pinfunction "K_2") (pintype "passive"))
      (node (ref "D243") (pin "2") (pinfunction "K_2") (pintype "passive"))
      (node (ref "D244") (pin "2") (pinfunction "K_2") (pintype "passive"))
      (node (ref "D245") (pin "2") (pinfunction "K_2") (pintype "passive"))
      (node (ref "D246") (pin "2") (pinfunction "K_2") (pintype "passive"))
      (node (ref "D247") (pin "2") (pinfunction "K_2") (pintype "passive"))
      (node (ref "D248") (pin "2") (pinfunction "K_2") (pintype "passive"))
      (node (ref "D249") (pin "2") (pinfunction "K_2") (pintype "passive"))
      (node (ref "D250") (pin "2") (pinfunction "K_2") (pintype "passive"))
      (node (ref "D251") (pin "2") (pinfunction "K_2") (pintype "passive"))
      (node (ref "D252") (pin "2") (pinfunction "K_2") (pintype "passive"))
      (node (ref "D253") (pin "2") (pinfunction "K_2") (pintype "passive"))
      (node (ref "D254") (pin "2") (pinfunction "K_2") (pintype "passive"))
      (node (ref "D255") (pin "2") (pinfunction "K_2") (pintype "passive"))
    )
    (net (code "19") (name "/row5") (class "Default")
      (node (ref "D241") (pin "2") (pinfunction "K_2") (pintype "passive"))
      (node (ref "D256") (pin "2") (pinfunction "K_2") (pintype "passive"))
      (node (ref "D257") (pin "2") (pinfunction "K_2") (pintype "passive"))
      (node (ref "D258") (pin "2") (pinfunction "K_2") (pintype "passive"))
      (node (ref "D260") (pin "2") (pinfunction "K_2") (pintype "passive"))
      (node (ref "D261") (pin "2") (pinfunction "K_2") (pintype "passive"))
      (node (ref "D262") (pin "2") (pinfunction "K_2") (pintype "passive"))
      (node (ref "D263") (pin "2") (pinfunction "K_2") (pintype "passive"))
      (node (ref "D264") (pin "2") (pinfunction "K_2") (pintype "passive"))
      (node (ref "D265") (pin "2") (pinfunction "K_2") (pintype "passive"))
      (node (ref "D266") (pin "2") (pinfunction "K_2") (pintype "passive"))
    )
    (net (code "20") (name "Net-(D201-A)") (class "Default")
      (node (ref "D201") (pin "1") (pinfunction "A_1") (pintype "passive"))
      (node (ref "S201") (pin "1") (pinfunction "1_1") (pintype "passive"))
    )
    (net (code "21") (name "Net-(D202-A)") (class "Default")
      (node (ref "D202") (pin "1") (pinfunction "A_1") (pintype "passive"))
      (node (ref "S202") (pin "1") (pinfunction "1_1") (pintype "passive"))
    )
    (net (code "22") (name "Net-(D203-A)") (class "Default")
      (node (ref "D203") (pin "1") (pinfunction "A_1") (pintype "passive"))
      (node (ref "S203") (pin "1") (pinfunction "1_1") (pintype "passive"))
    )
    (net (code "23") (name "Net-(D204-A)") (class "Default")
      (node (ref "D204") (pin "1") (pinfunction "A_1") (pintype "passive"))
      (node (ref "S204") (pin "1") (pinfunction "1_1") (pintype "passive"))
    )
    (net (code "24") (name "Net-(D205-A)") (class "Default")
      (node (ref "D205") (pin "1") (pinfunction "A_1") (pintype "passive"))
      (node (ref "S205") (pin "1") (pinfunction "1_1") (pintype "passive"))
    )
    (net (code "25") (name "Net-(D206-A)") (class "Default")
      (node (ref "D206") (pin "1") (pinfunction "A_1") (pintype "passive"))
      (node (ref "S206") (pin "1") (pinfunction "1_1") (pintype "passive"))
    )
    (net (code "26") (name "Net-(D207-A)") (class "Default")
      (node (ref "D207") (pin "1") (pinfunction "A_1") (pintype "passive"))
      (node (ref "S207") (pin "1") (pinfunction "1_1") (pintype "passive"))
    )
    (net (code "27") (name "Net-(D208-A)") (class "Default")
      (node (ref "D208") (pin "1") (pinfunction "A_1") (pintype "passive"))
      (node (ref "S208") (pin "1") (pinfunction "1_1") (pintype "passive"))
    )
    (net (code "28") (name "Net-(D209-A)") (class "Default")
      (node (ref "D209") (pin "1") (pinfunction "A_1") (pintype "passive"))
      (node (ref "S209") (pin "1") (pinfunction "1_1") (pintype "passive"))
    )
    (net (code "29") (name "Net-(D210-A)") (class "Default")
      (node (ref "D210") (pin "1") (pinfunction "A_1") (pintype "passive"))
      (node (ref "S210") (pin "1") (pinfunction "1_1") (pintype "passive"))
    )
    (net (code "30") (name "Net-(D211-A)") (class "Default")
      (node (ref "D211") (pin "1") (pinfunction "A_1") (pintype "passive"))
      (node (ref "S211") (pin "1") (pinfunction "1_1") (pintype "passive"))
    )
    (net (code "31") (name "Net-(D212-A)") (class "Default")
      (node (ref "D212") (pin "1") (pinfunction "A_1") (pintype "passive"))
      (node (ref "S212") (pin "1") (pinfunction "1_1") (pintype "passive"))
    )
    (net (code "32") (name "Net-(D213-A)") (class "Default")
      (node (ref "D213") (pin "1") (pinfunction "A_1") (pintype "passive"))
      (node (ref "S213") (pin "1") (pinfunction "1_1") (pintype "passive"))
    )
    (net (code "33") (name "Net-(D214-A)") (class "Default")
      (node (ref "D214") (pin "1") (pinfunction "A_1") (pintype "passive"))
      (node (ref "S214") (pin "1") (pinfunction "1_1") (pintype "passive"))
    )
    (net (code "34") (name "Net-(D215-A)") (class "Default")
      (node (ref "D215") (pin "1") (pinfunction "A_1") (pintype "passive"))
      (node (ref "S215") (pin "1") (pinfunction "1_1") (pintype "passive"))
    )
    (net (code "35") (name "Net-(D216-A)") (class "Default")
      (node (ref "D216") (pin "1") (pinfunction "A_1") (pintype "passive"))
      (node (ref "S216") (pin "1") (pinfunction "1_1") (pintype "passive"))
    )
    (net (code "36") (name "Net-(D217-A)") (class "Default")
      (node (ref "D217") (pin "1") (pinfunction "A_1") (pintype "passive"))
      (node (ref "S217") (pin "1") (pinfunction "1_1") (pintype "passive"))
    )
    (net (code "37") (name "Net-(D218-A)") (class "Default")
      (node (ref "D218") (pin "1") (pinfunction "A_1") (pintype "passive"))
      (node (ref "S218") (pin "1") (pinfunction "1_1") (pintype "passive"))
    )
    (net (code "38") (name "Net-(D219-A)") (class "Default")
      (node (ref "D219") (pin "1") (pinfunction "A_1") (pintype "passive"))
      (node (ref "S219") (pin "1") (pinfunction "1_1") (pintype "passive"))
    )
    (net (code "39") (name "Net-(D220-A)") (class "Default")
      (node (ref "D220") (pin "1") (pinfunction "A_1") (pintype "passive"))
      (node (ref "S220") (pin "1") (pinfunction "1_1") (pintype "passive"))
    )
    (net (code "40") (name "Net-(D221-A)") (class "Default")
      (node (ref "D221") (pin "1") (pinfunction "A_1") (pintype "passive"))
      (node (ref "S221") (pin "1") (pinfunction "1_1") (pintype "passive"))
    )
    (net (code "41") (name "Net-(D222-A)") (class "Default")
      (node (ref "D222") (pin "1") (pinfunction "A_1") (pintype "passive"))
      (node (ref "S222") (pin "1") (pinfunction "1_1") (pintype "passive"))
    )
    (net (code "42") (name "Net-(D223-A)") (class "Default")
      (node (ref "D223") (pin "1") (pinfunction "A_1") (pintype "passive"))
      (node (ref "S223") (pin "1") (pinfunction "1_1") (pintype "passive"))
    )
    (net (code "43") (name "Net-(D224-A)") (class "Default")
      (node (ref "D224") (pin "1") (pinfunction "A_1") (pintype "passive"))
      (node (ref "S224") (pin "1") (pinfunction "1_1") (pintype "passive"))
    )
    (net (code "44") (name "Net-(D225-A)") (class "Default")
      (node (ref "D225") (pin "1") (pinfunction "A_1") (pintype "passive"))
      (node (ref "S225") (pin "1") (pinfunction "1_1") (pintype "passive"))
    )
    (net (code "45") (name "Net-(D226-A)") (class "Default")
      (node (ref "D226") (pin "1") (pinfunction "A_1") (pintype "passive"))
      (node (ref "S226") (pin "1") (pinfunction "1_1") (pintype "passive"))
    )
    (net (code "46") (name "Net-(D227-A)") (class "Default")
      (node (ref "D227") (pin "1") (pinfunction "A_1") (pintype "passive"))
      (node (ref "S227") (pin "1") (pinfunction "1_1") (pintype "passive"))
    )
    (net (code "47") (name "Net-(D228-A)") (class "Default")
      (node (ref "D228") (pin "1") (pinfunction "A_1") (pintype "passive"))
      (node (ref "S228") (pin "1") (pinfunction "1_1") (pintype "passive"))
    )
    (net (code "48") (name "Net-(D228_2-A)") (class "Default")
      (node (ref "D228_2") (pin "1") (pinfunction "A_1") (pintype "passive"))
      (node (ref "S228_2") (pin "1") (pinfunction "1_1") (pintype "passive"))
    )
    (net (code "49") (name "Net-(D229-A)") (class "Default")
      (node (ref "D229") (pin "1") (pinfunction "A_1") (pintype "passive"))
      (node (ref "S229") (pin "2") (pinfunction "2_2") (pintype "passive"))
    )
    (net (code "50") (name "Net-(D230-A)") (class "Default")
      (node (ref "D230") (pin "1") (pinfunction "A_1") (pintype "passive"))
      (node (ref "S230") (pin "1") (pinfunction "1_1") (pintype "passive"))
    )
    (net (code "51") (name "Net-(D231-A)") (class "Default")
      (node (ref "D231") (pin "1") (pinfunction "A_1") (pintype "passive"))
      (node (ref "S231") (pin "1") (pinfunction "1_1") (pintype "passive"))
    )
    (net (code "52") (name "Net-(D232-A)") (class "Default")
      (node (ref "D232") (pin "1") (pinfunction "A_1") (pintype "passive"))
      (node (ref "S232") (pin "1") (pinfunction "1_1") (pintype "passive"))
    )
    (net (code "53") (name "Net-(D233-A)") (class "Default")
      (node (ref "D233") (pin "1") (pinfunction "A_1") (pintype "passive"))
      (node (ref "S233") (pin "1") (pinfunction "1_1") (pintype "passive"))
    )
    (net (code "54") (name "Net-(D234-A)") (class "Default")
      (node (ref "D234") (pin "1") (pinfunction "A_1") (pintype "passive"))
      (node (ref "S234") (pin "1") (pinfunction "1_1") (pintype "passive"))
    )
    (net (code "55") (name "Net-(D235-A)") (class "Default")
      (node (ref "D235") (pin "1") (pinfunction "A_1") (pintype "passive"))
      (node (ref "S235") (pin "1") (pinfunction "1_1") (pintype "passive"))
    )
    (net (code "56") (name "Net-(D236-A)") (class "Default")
      (node (ref "D236") (pin "1") (pinfunction "A_1") (pintype "passive"))
      (node (ref "S236") (pin "1") (pinfunction "1_1") (pintype "passive"))
    )
    (net (code "57") (name "Net-(D237-A)") (class "Default")
      (node (ref "D237") (pin "1") (pinfunction "A_1") (pintype "passive"))
      (node (ref "S237") (pin "1") (pinfunction "1_1") (pintype "passive"))
    )
    (net (code "58") (name "Net-(D238-A)") (class "Default")
      (node (ref "D238") (pin "1") (pinfunction "A_1") (pintype "passive"))
      (node (ref "S238") (pin "1") (pinfunction "1_1") (pintype "passive"))
    )
    (net (code "59") (name "Net-(D239-A)") (class "Default")
      (node (ref "D239") (pin "1") (pinfunction "A_1") (pintype "passive"))
      (node (ref "S239") (pin "1") (pinfunction "1_1") (pintype "passive"))
    )
    (net (code "60") (name "Net-(D240-A)") (class "Default")
      (node (ref "D240") (pin "1") (pinfunction "A_1") (pintype "passive"))
      (node (ref "S240") (pin "1") (pinfunction "1_1") (pintype "passive"))
    )
    (net (code "61") (name "Net-(D241-A)") (class "Default")
      (node (ref "D241") (pin "1") (pinfunction "A_1") (pintype "passive"))
      (node (ref "S241") (pin "2") (pinfunction "2_2") (pintype "passive"))
    )
    (net (code "62") (name "Net-(D242-A)") (class "Default")
      (node (ref "D242") (pin "1") (pinfunction "A_1") (pintype "passive"))
      (node (ref "S242") (pin "1") (pinfunction "1_1") (pintype "passive"))
    )
    (net (code "63") (name "Net-(D243-A)") (class "Default")
      (node (ref "D243") (pin "1") (pinfunction "A_1") (pintype "passive"))
      (node (ref "S243") (pin "1") (pinfunction "1_1") (pintype "passive"))
    )
    (net (code "64") (name "Net-(D244-A)") (class "Default")
      (node (ref "D244") (pin "1") (pinfunction "A_1") (pintype "passive"))
      (node (ref "S244") (pin "2") (pinfunction "2_2") (pintype "passive"))
    )
    (net (code "65") (name "Net-(D245-A)") (class "Default")
      (node (ref "D245") (pin "1") (pinfunction "A_1") (pintype "passive"))
      (node (ref "S245") (pin "1") (pinfunction "1_1") (pintype "passive"))
    )
    (net (code "66") (name "Net-(D246-A)") (class "Default")
      (node (ref "D246") (pin "1") (pinfunction "A_1") (pintype "passive"))
      (node (ref "S246") (pin "1") (pinfunction "1_1") (pintype "passive"))
    )
    (net (code "67") (name "Net-(D247-A)") (class "Default")
      (node (ref "D247") (pin "1") (pinfunction "A_1") (pintype "passive"))
      (node (ref "S247") (pin "1") (pinfunction "1_1") (pintype "passive"))
    )
    (net (code "68") (name "Net-(D248-A)") (class "Default")
      (node (ref "D248") (pin "1") (pinfunction "A_1") (pintype "passive"))
      (node (ref "S248") (pin "1") (pinfunction "1_1") (pintype "passive"))
    )
    (net (code "69") (name "Net-(D249-A)") (class "Default")
      (node (ref "D249") (pin "1") (pinfunction "A_1") (pintype "passive"))
      (node (ref "S249") (pin "1") (pinfunction "1_1") (pintype "passive"))
    )
    (net (code "70") (name "Net-(D250-A)") (class "Default")
      (node (ref "D250") (pin "1") (pinfunction "A_1") (pintype "passive"))
      (node (ref "S250") (pin "1") (pinfunction "1_1") (pintype "passive"))
    )
    (net (code "71") (name "Net-(D251-A)") (class "Default")
      (node (ref "D251") (pin "1") (pinfunction "A_1") (pintype "passive"))
      (node (ref "S251") (pin "1") (pinfunction "1_1") (pintype "passive"))
    )
    (net (code "72") (name "Net-(D252-A)") (class "Default")
      (node (ref "D252") (pin "1") (pinfunction "A_1") (pintype "passive"))
      (node (ref "S252") (pin "1") (pinfunction "1_1") (pintype "passive"))
    )
    (net (code "73") (name "Net-(D253-A)") (class "Default")
      (node (ref "D253") (pin "1") (pinfunction "A_1") (pintype "passive"))
      (node (ref "S253") (pin "1") (pinfunction "1_1") (pintype "passive"))
    )
    (net (code "74") (name "Net-(D254-A)") (class "Default")
      (node (ref "D254") (pin "1") (pinfunction "A_1") (pintype "passive"))
      (node (ref "S254") (pin "1") (pinfunction "1_1") (pintype "passive"))
    )
    (net (code "75") (name "Net-(D255-A)") (class "Default")
      (node (ref "D255") (pin "1") (pinfunction "A_1") (pintype "passive"))
      (node (ref "S256") (pin "1") (pinfunction "1_1") (pintype "passive"))
    )
    (net (code "76") (name "Net-(D256-A)") (class "Default")
      (node (ref "D256") (pin "1") (pinfunction "A_1") (pintype "passive"))
      (node (ref "S269") (pin "1") (pinfunction "1_1") (pintype "passive"))
    )
    (net (code "77") (name "Net-(D257-A)") (class "Default")
      (node (ref "D257") (pin "1") (pinfunction "A_1") (pintype "passive"))
      (node (ref "S257") (pin "2") (pinfunction "2_2") (pintype "passive"))
    )
    (net (code "78") (name "Net-(D258-A)") (class "Default")
      (node (ref "D258") (pin "1") (pinfunction "A_1") (pintype "passive"))
      (node (ref "S258") (pin "1") (pinfunction "1_1") (pintype "passive"))
    )
    (net (code "79") (name "Net-(D259-A)") (class "Default")
      (node (ref "D259") (pin "1") (pinfunction "A_1") (pintype "passive"))
      (node (ref "S259") (pin "1") (pinfunction "1_1") (pintype "passive"))
    )
    (net (code "80") (name "Net-(D260-A)") (class "Default")
      (node (ref "D260") (pin "1") (pinfunction "A_1") (pintype "passive"))
      (node (ref "S260") (pin "1") (pinfunction "1_1") (pintype "passive"))
    )
    (net (code "81") (name "Net-(D261-A)") (class "Default")
      (node (ref "D261") (pin "1") (pinfunction "A_1") (pintype "passive"))
      (node (ref "S261") (pin "1") (pinfunction "1_1") (pintype "passive"))
      (node (ref "S261_1") (pin "1") (pinfunction "1_1") (pintype "passive"))
    )
    (net (code "82") (name "Net-(D262-A)") (class "Default")
      (node (ref "D262") (pin "1") (pinfunction "A_1") (pintype "passive"))
      (node (ref "S262") (pin "2") (pinfunction "2_2") (pintype "passive"))
    )
    (net (code "83") (name "Net-(D263-A)") (class "Default")
      (node (ref "D263") (pin "1") (pinfunction "A_1") (pintype "passive"))
      (node (ref "S263") (pin "2") (pinfunction "2_2") (pintype "passive"))
      (node (ref "S263_1") (pin "2") (pinfunction "2_2") (pintype "passive"))
    )
    (net (code "84") (name "Net-(D264-A)") (class "Default")
      (node (ref "D264") (pin "1") (pinfunction "A_1") (pintype "passive"))
      (node (ref "S264") (pin "1") (pinfunction "1_1") (pintype "passive"))
    )
    (net (code "85") (name "Net-(D265-A)") (class "Default")
      (node (ref "D265") (pin "1") (pinfunction "A_1") (pintype "passive"))
      (node (ref "S265") (pin "2") (pinfunction "2_2") (pintype "passive"))
    )
    (net (code "86") (name "Net-(D266-A)") (class "Default")
      (node (ref "D266") (pin "1") (pinfunction "A_1") (pintype "passive"))
      (node (ref "S266") (pin "1") (pinfunction "1_1") (pintype "passive"))
    )
    (net (code "87") (name "unconnected-(STAB1-Pad1)") (class "Default")
      (node (ref "STAB1") (pin "1") (pinfunction "1_1") (pintype "passive"))
    )
  )
)
